# Sheet1.net
KiCad netlist of a schematic drawn in Altium Designer
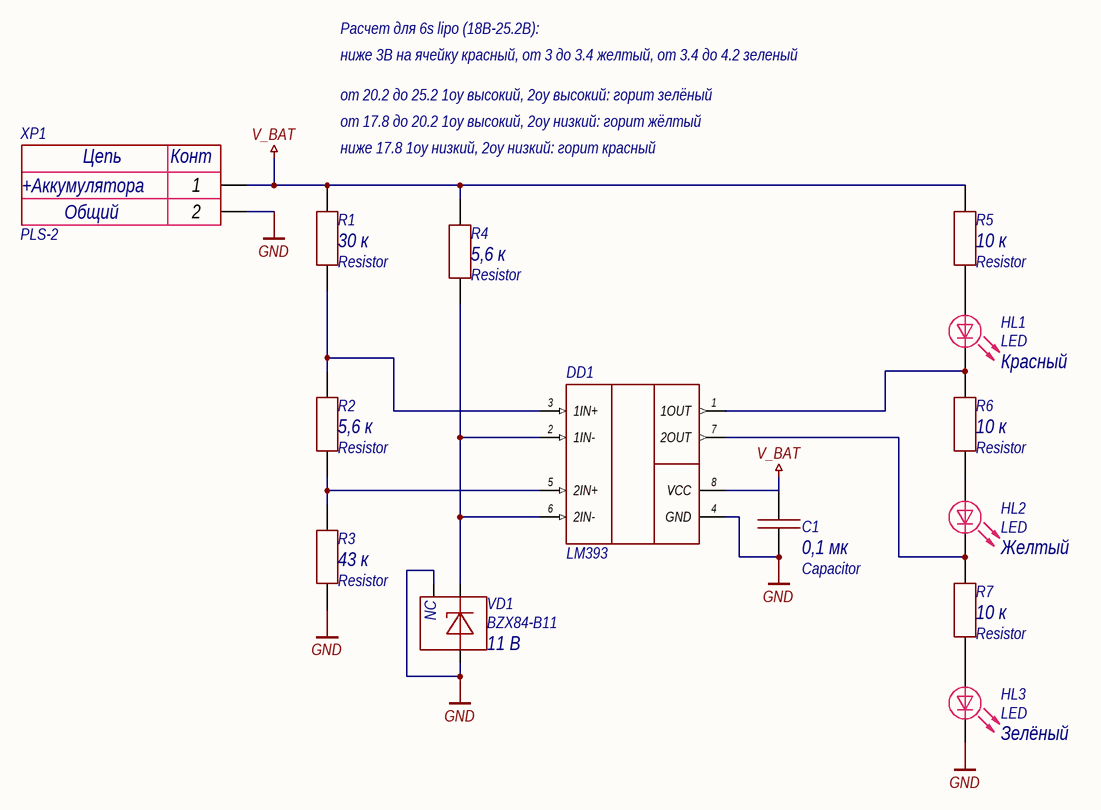
[diagram p0: Sheet1.SchDoc]

(export (version "E")
  (design (tool "Eeschema 10.0.6"))
  (components
    (comp (ref "C1")
      (value "Capacitor")
      (footprint "0603C")
      (description "Конденсатор")
      (fields
        (field (name "ALTIUM_VALUE") "0,1 мк")
        (field (name "PART NUMBER") "Capacitor_0,1u_10_50V_X7R_0603C")
        (field (name "TOLERANCE") "0,1")
      )
      (libsource (lib "Hydrolib") (part "Capacitor"))
    )
    (comp (ref "DD1")
      (value "LM393")
      (footprint "SOIC-8")
      (description "Двойной маломощный компаратор напряжения")
      (fields (field (name "MF") "Texas Instruments") (field (name "MP") "LM393D"))
      (libsource (lib "Hydrolib") (part "LM393"))
    )
    (comp (ref "HL1")
      (value "LED")
      (footprint "0805D")
      (description "Светодиод")
      (fields (field (name "COLOR") "Красный"))
      (libsource (lib "Hydrolib") (part "LED"))
    )
    (comp (ref "HL2")
      (value "LED")
      (footprint "0805D")
      (description "Светодиод")
      (fields (field (name "COLOR") "Желтый"))
      (libsource (lib "Hydrolib") (part "LED"))
    )
    (comp (ref "HL3")
      (value "LED")
      (footprint "0805D")
      (description "Светодиод")
      (fields (field (name "COLOR") "Зелёный"))
      (libsource (lib "Hydrolib") (part "LED"))
    )
    (comp (ref "R1")
      (value "Resistor")
      (footprint "0603R")
      (description "Резистор номиналом 30 кОм и точностью 1%")
      (fields
        (field (name "ALTIUM_VALUE") "30 к")
        (field (name "PART NUMBER") "Resistor_30k_1_0603")
        (field (name "TOLERANCE") "1%")
      )
      (libsource (lib "Hydrolib") (part "Resistor"))
    )
    (comp (ref "R2")
      (value "Resistor")
      (footprint "0603R")
      (description "Резистор номиналом 5,6 кОм и точностью 1%")
      (fields
        (field (name "ALTIUM_VALUE") "5,6 к")
        (field (name "PART NUMBER") "Resistor_5.6k_1_0603")
        (field (name "TOLERANCE") "1%")
      )
      (libsource (lib "Hydrolib") (part "Resistor"))
    )
    (comp (ref "R3")
      (value "Resistor")
      (footprint "0603R")
      (description "Резистор номиналом 43 кОм и точностью 1%")
      (fields
        (field (name "ALTIUM_VALUE") "43 к")
        (field (name "PART NUMBER") "Resistor_43k_1_0603")
        (field (name "TOLERANCE") "1%")
      )
      (libsource (lib "Hydrolib") (part "Resistor"))
    )
    (comp (ref "R4")
      (value "Resistor")
      (footprint "0603R")
      (description "Резистор номиналом 5,6 кОм и точностью 1%")
      (fields
        (field (name "ALTIUM_VALUE") "5,6 к")
        (field (name "PART NUMBER") "Resistor_5.6k_1_0603")
        (field (name "TOLERANCE") "1%")
      )
      (libsource (lib "Hydrolib") (part "Resistor"))
    )
    (comp (ref "R5")
      (value "Resistor")
      (footprint "0603R")
      (description "Резистор номиналом 10 кОм и точностью 1%")
      (fields
        (field (name "ALTIUM_VALUE") "10 к")
        (field (name "PART NUMBER") "Resistor_10k_1_0603")
        (field (name "TOLERANCE") "1%")
      )
      (libsource (lib "Hydrolib") (part "Resistor"))
    )
    (comp (ref "R6")
      (value "Resistor")
      (footprint "0603R")
      (description "Резистор номиналом 10 кОм и точностью 1%")
      (fields
        (field (name "ALTIUM_VALUE") "10 к")
        (field (name "PART NUMBER") "Resistor_10k_1_0603")
        (field (name "TOLERANCE") "1%")
      )
      (libsource (lib "Hydrolib") (part "Resistor"))
    )
    (comp (ref "R7")
      (value "Resistor")
      (footprint "0603R")
      (description "Резистор номиналом 10 кОм и точностью 1%")
      (fields
        (field (name "ALTIUM_VALUE") "10 к")
        (field (name "PART NUMBER") "Resistor_10k_1_0603")
        (field (name "TOLERANCE") "1%")
      )
      (libsource (lib "Hydrolib") (part "Resistor"))
    )
    (comp (ref "VD1")
      (value "BZX84-B11")
      (footprint "SOT23-3")
      (description "Стабилитрон на 11 В, рассеиваемая мощность 0.25 Вт")
      (fields (field (name "ALTIUM_VALUE") "11 В"))
      (libsource (lib "Hydrolib") (part "Zener_3pin"))
    )
    (comp (ref "XP1")
      (value "PLS-2")
      (footprint "PLS2")
      (description "+Аккумулятора")
      (fields (field (name "VALUE2") "Общий") (field (name "VALUE1") "+Аккумулятора"))
      (libsource (lib "Hydrolib") (part "Conn_2pin"))
    )
  )
  (nets
    (net (code "1") (name "GND") (class "Default")
      (node (ref "C1") (pin "1") (pinfunction "1_1") (pintype "passive"))
      (node (ref "DD1") (pin "4") (pinfunction "GND_4") (pintype "power_in"))
      (node (ref "HL3") (pin "2") (pinfunction "2_2") (pintype "passive"))
      (node (ref "R3") (pin "1") (pinfunction "1_1") (pintype "passive"))
      (node (ref "VD1") (pin "1") (pinfunction "1_1") (pintype "passive"))
      (node (ref "VD1") (pin "2") (pinfunction "2_2") (pintype "passive"))
      (node (ref "XP1") (pin "2") (pinfunction "2_2") (pintype "passive"))
    )
    (net (code "2") (name "Net-(DD1-1IN+)") (class "Default")
      (node (ref "DD1") (pin "3") (pinfunction "1IN+_3") (pintype "input"))
      (node (ref "R1") (pin "1") (pinfunction "1_1") (pintype "passive"))
      (node (ref "R2") (pin "2") (pinfunction "2_2") (pintype "passive"))
    )
    (net (code "3") (name "Net-(DD1-1IN-)") (class "Default")
      (node (ref "DD1") (pin "2") (pinfunction "1IN-_2") (pintype "input"))
      (node (ref "DD1") (pin "6") (pinfunction "2IN-_6") (pintype "input"))
      (node (ref "R4") (pin "1") (pinfunction "1_1") (pintype "passive"))
      (node (ref "VD1") (pin "3") (pinfunction "3_3") (pintype "passive"))
    )
    (net (code "4") (name "Net-(DD1-1OUT)") (class "Default")
      (node (ref "DD1") (pin "1") (pinfunction "1OUT_1") (pintype "output"))
      (node (ref "HL1") (pin "2") (pinfunction "2_2") (pintype "passive"))
      (node (ref "R6") (pin "2") (pinfunction "2_2") (pintype "passive"))
    )
    (net (code "5") (name "Net-(DD1-2IN+)") (class "Default")
      (node (ref "DD1") (pin "5") (pinfunction "2IN+_5") (pintype "input"))
      (node (ref "R2") (pin "1") (pinfunction "1_1") (pintype "passive"))
      (node (ref "R3") (pin "2") (pinfunction "2_2") (pintype "passive"))
    )
    (net (code "6") (name "Net-(DD1-2OUT)") (class "Default")
      (node (ref "DD1") (pin "7") (pinfunction "2OUT_7") (pintype "output"))
      (node (ref "HL2") (pin "2") (pinfunction "2_2") (pintype "passive"))
      (node (ref "R7") (pin "2") (pinfunction "2_2") (pintype "passive"))
    )
    (net (code "7") (name "Net-(HL1-Pad1)") (class "Default")
      (node (ref "HL1") (pin "1") (pinfunction "1_1") (pintype "passive"))
      (node (ref "R5") (pin "1") (pinfunction "1_1") (pintype "passive"))
    )
    (net (code "8") (name "Net-(HL2-Pad1)") (class "Default")
      (node (ref "HL2") (pin "1") (pinfunction "1_1") (pintype "passive"))
      (node (ref "R6") (pin "1") (pinfunction "1_1") (pintype "passive"))
    )
    (net (code "9") (name "Net-(HL3-Pad1)") (class "Default")
      (node (ref "HL3") (pin "1") (pinfunction "1_1") (pintype "passive"))
      (node (ref "R7") (pin "1") (pinfunction "1_1") (pintype "passive"))
    )
    (net (code "10") (name "V_BAT") (class "Default")
      (node (ref "C1") (pin "2") (pinfunction "2_2") (pintype "passive"))
      (node (ref "DD1") (pin "8") (pinfunction "VCC_8") (pintype "power_in"))
      (node (ref "R1") (pin "2") (pinfunction "2_2") (pintype "passive"))
      (node (ref "R4") (pin "2") (pinfunction "2_2") (pintype "passive"))
      (node (ref "R5") (pin "2") (pinfunction "2_2") (pintype "passive"))
      (node (ref "XP1") (pin "1") (pinfunction "1_1") (pintype "passive"))
    )
  )
)
